# solenoidcontroller.net
KiCad netlist of a schematic drawn in EAGLE
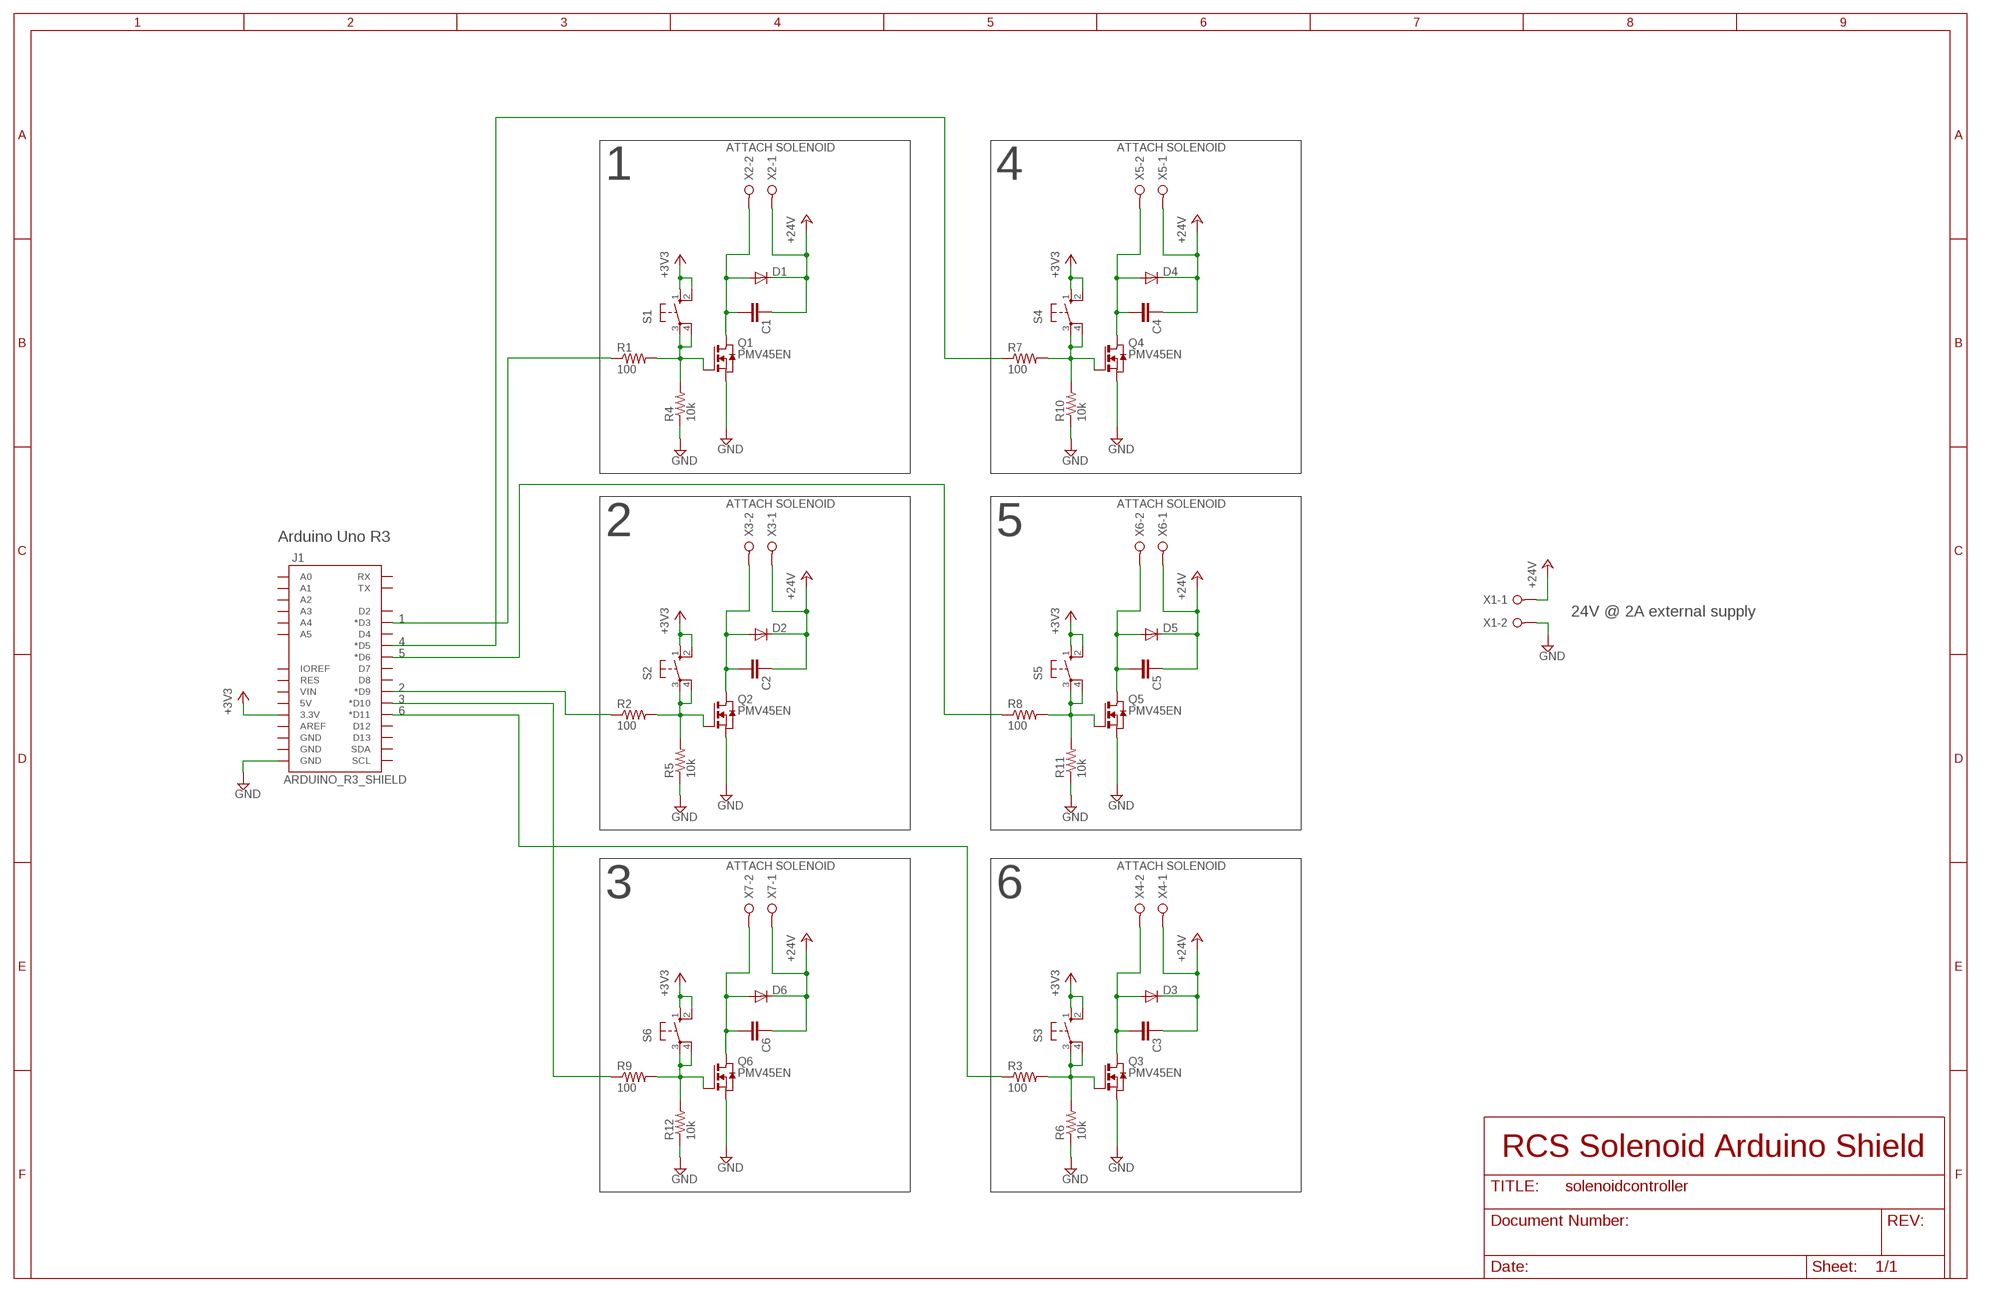
[diagram p0: schematic, sheet 1]

(export (version "E")
  (design (tool "Eeschema 10.0.6"))
  (components
    (comp (ref "C1")
      (value "C-EUC0603")
      (footprint "eagle-import:C0603")
      (libsource (lib "eagle-import") (part "C-EUC0603"))
    )
    (comp (ref "C2")
      (value "C-EUC0603")
      (footprint "eagle-import:C0603")
      (libsource (lib "eagle-import") (part "C-EUC0603"))
    )
    (comp (ref "C3")
      (value "C-EUC0603")
      (footprint "eagle-import:C0603")
      (libsource (lib "eagle-import") (part "C-EUC0603"))
    )
    (comp (ref "C4")
      (value "C-EUC0603")
      (footprint "eagle-import:C0603")
      (libsource (lib "eagle-import") (part "C-EUC0603"))
    )
    (comp (ref "C5")
      (value "C-EUC0603")
      (footprint "eagle-import:C0603")
      (libsource (lib "eagle-import") (part "C-EUC0603"))
    )
    (comp (ref "C6")
      (value "C-EUC0603")
      (footprint "eagle-import:C0603")
      (libsource (lib "eagle-import") (part "C-EUC0603"))
    )
    (comp (ref "D1")
      (value "DIODE-DO214BA")
      (footprint "eagle-import:DO214BA")
      (libsource (lib "eagle-import") (part "DIODE-DO214BA"))
    )
    (comp (ref "D2")
      (value "DIODE-DO214BA")
      (footprint "eagle-import:DO214BA")
      (libsource (lib "eagle-import") (part "DIODE-DO214BA"))
    )
    (comp (ref "D3")
      (value "DIODE-DO214BA")
      (footprint "eagle-import:DO214BA")
      (libsource (lib "eagle-import") (part "DIODE-DO214BA"))
    )
    (comp (ref "D4")
      (value "DIODE-DO214BA")
      (footprint "eagle-import:DO214BA")
      (libsource (lib "eagle-import") (part "DIODE-DO214BA"))
    )
    (comp (ref "D5")
      (value "DIODE-DO214BA")
      (footprint "eagle-import:DO214BA")
      (libsource (lib "eagle-import") (part "DIODE-DO214BA"))
    )
    (comp (ref "D6")
      (value "DIODE-DO214BA")
      (footprint "eagle-import:DO214BA")
      (libsource (lib "eagle-import") (part "DIODE-DO214BA"))
    )
    (comp (ref "J1")
      (value "ARDUINO_R3_SHIELD")
      (footprint "eagle-import:UNO_R3_SHIELD")
      (libsource (lib "eagle-import") (part "ARDUINO_R3_SHIELD"))
    )
    (comp (ref "Q1")
      (value "PMV45EN")
      (footprint "eagle-import:SOT23")
      (libsource (lib "eagle-import") (part "PMV45EN"))
    )
    (comp (ref "Q2")
      (value "PMV45EN")
      (footprint "eagle-import:SOT23")
      (libsource (lib "eagle-import") (part "PMV45EN"))
    )
    (comp (ref "Q3")
      (value "PMV45EN")
      (footprint "eagle-import:SOT23")
      (libsource (lib "eagle-import") (part "PMV45EN"))
    )
    (comp (ref "Q4")
      (value "PMV45EN")
      (footprint "eagle-import:SOT23")
      (libsource (lib "eagle-import") (part "PMV45EN"))
    )
    (comp (ref "Q5")
      (value "PMV45EN")
      (footprint "eagle-import:SOT23")
      (libsource (lib "eagle-import") (part "PMV45EN"))
    )
    (comp (ref "Q6")
      (value "PMV45EN")
      (footprint "eagle-import:SOT23")
      (libsource (lib "eagle-import") (part "PMV45EN"))
    )
    (comp (ref "R1")
      (value "100")
      (footprint "eagle-import:R0603")
      (libsource (lib "eagle-import") (part "R-US_R0603"))
    )
    (comp (ref "R2")
      (value "100")
      (footprint "eagle-import:R0603")
      (libsource (lib "eagle-import") (part "R-US_R0603"))
    )
    (comp (ref "R3")
      (value "100")
      (footprint "eagle-import:R0603")
      (libsource (lib "eagle-import") (part "R-US_R0603"))
    )
    (comp (ref "R4")
      (value "10k")
      (footprint "eagle-import:R0603")
      (libsource (lib "eagle-import") (part "R-US_R0603"))
    )
    (comp (ref "R5")
      (value "10k")
      (footprint "eagle-import:R0603")
      (libsource (lib "eagle-import") (part "R-US_R0603"))
    )
    (comp (ref "R6")
      (value "10k")
      (footprint "eagle-import:R0603")
      (libsource (lib "eagle-import") (part "R-US_R0603"))
    )
    (comp (ref "R7")
      (value "100")
      (footprint "eagle-import:R0603")
      (libsource (lib "eagle-import") (part "R-US_R0603"))
    )
    (comp (ref "R8")
      (value "100")
      (footprint "eagle-import:R0603")
      (libsource (lib "eagle-import") (part "R-US_R0603"))
    )
    (comp (ref "R9")
      (value "100")
      (footprint "eagle-import:R0603")
      (libsource (lib "eagle-import") (part "R-US_R0603"))
    )
    (comp (ref "R10")
      (value "10k")
      (footprint "eagle-import:R0603")
      (libsource (lib "eagle-import") (part "R-US_R0603"))
    )
    (comp (ref "R11")
      (value "10k")
      (footprint "eagle-import:R0603")
      (libsource (lib "eagle-import") (part "R-US_R0603"))
    )
    (comp (ref "R12")
      (value "10k")
      (footprint "eagle-import:R0603")
      (libsource (lib "eagle-import") (part "R-US_R0603"))
    )
    (comp (ref "S1")
      (value "10-XX")
      (footprint "eagle-import:B3F-10XX")
      (fields (field (name "MPN") "B3F-1000"))
      (libsource (lib "eagle-import") (part "10-XX"))
    )
    (comp (ref "S2")
      (value "10-XX")
      (footprint "eagle-import:B3F-10XX")
      (fields (field (name "MPN") "B3F-1000"))
      (libsource (lib "eagle-import") (part "10-XX"))
    )
    (comp (ref "S3")
      (value "10-XX")
      (footprint "eagle-import:B3F-10XX")
      (fields (field (name "MPN") "B3F-1000"))
      (libsource (lib "eagle-import") (part "10-XX"))
    )
    (comp (ref "S4")
      (value "10-XX")
      (footprint "eagle-import:B3F-10XX")
      (fields (field (name "MPN") "B3F-1000"))
      (libsource (lib "eagle-import") (part "10-XX"))
    )
    (comp (ref "S5")
      (value "10-XX")
      (footprint "eagle-import:B3F-10XX")
      (fields (field (name "MPN") "B3F-1000"))
      (libsource (lib "eagle-import") (part "10-XX"))
    )
    (comp (ref "S6")
      (value "10-XX")
      (footprint "eagle-import:B3F-10XX")
      (fields (field (name "MPN") "B3F-1000"))
      (libsource (lib "eagle-import") (part "10-XX"))
    )
    (comp (ref "X1")
      (value "W237-02P")
      (footprint "eagle-import:W237-132")
      (libsource (lib "eagle-import") (part "W237-02P"))
    )
    (comp (ref "X2")
      (value "W237-02P")
      (footprint "eagle-import:W237-132")
      (libsource (lib "eagle-import") (part "W237-02P"))
    )
    (comp (ref "X3")
      (value "W237-02P")
      (footprint "eagle-import:W237-132")
      (libsource (lib "eagle-import") (part "W237-02P"))
    )
    (comp (ref "X4")
      (value "W237-02P")
      (footprint "eagle-import:W237-132")
      (libsource (lib "eagle-import") (part "W237-02P"))
    )
    (comp (ref "X5")
      (value "W237-02P")
      (footprint "eagle-import:W237-132")
      (libsource (lib "eagle-import") (part "W237-02P"))
    )
    (comp (ref "X6")
      (value "W237-02P")
      (footprint "eagle-import:W237-132")
      (libsource (lib "eagle-import") (part "W237-02P"))
    )
    (comp (ref "X7")
      (value "W237-02P")
      (footprint "eagle-import:W237-132")
      (libsource (lib "eagle-import") (part "W237-02P"))
    )
  )
  (nets
    (net (code "1") (name "+3V3") (class "Default")
      (node (ref "J1") (pin "3.3V") (pinfunction "3.3V_3.3V") (pintype "bidirectional"))
      (node (ref "S1") (pin "1") (pinfunction "S_1") (pintype "passive"))
      (node (ref "S1") (pin "2") (pinfunction "S1_2") (pintype "passive"))
      (node (ref "S2") (pin "1") (pinfunction "S_1") (pintype "passive"))
      (node (ref "S2") (pin "2") (pinfunction "S1_2") (pintype "passive"))
      (node (ref "S3") (pin "1") (pinfunction "S_1") (pintype "passive"))
      (node (ref "S3") (pin "2") (pinfunction "S1_2") (pintype "passive"))
      (node (ref "S4") (pin "1") (pinfunction "S_1") (pintype "passive"))
      (node (ref "S4") (pin "2") (pinfunction "S1_2") (pintype "passive"))
      (node (ref "S5") (pin "1") (pinfunction "S_1") (pintype "passive"))
      (node (ref "S5") (pin "2") (pinfunction "S1_2") (pintype "passive"))
      (node (ref "S6") (pin "1") (pinfunction "S_1") (pintype "passive"))
      (node (ref "S6") (pin "2") (pinfunction "S1_2") (pintype "passive"))
    )
    (net (code "2") (name "+24V") (class "Default")
      (node (ref "C1") (pin "1") (pinfunction "1_1") (pintype "passive"))
      (node (ref "C2") (pin "1") (pinfunction "1_1") (pintype "passive"))
      (node (ref "C3") (pin "1") (pinfunction "1_1") (pintype "passive"))
      (node (ref "C4") (pin "1") (pinfunction "1_1") (pintype "passive"))
      (node (ref "C5") (pin "1") (pinfunction "1_1") (pintype "passive"))
      (node (ref "C6") (pin "1") (pinfunction "1_1") (pintype "passive"))
      (node (ref "D1") (pin "C") (pinfunction "C_C") (pintype "passive"))
      (node (ref "D2") (pin "C") (pinfunction "C_C") (pintype "passive"))
      (node (ref "D3") (pin "C") (pinfunction "C_C") (pintype "passive"))
      (node (ref "D4") (pin "C") (pinfunction "C_C") (pintype "passive"))
      (node (ref "D5") (pin "C") (pinfunction "C_C") (pintype "passive"))
      (node (ref "D6") (pin "C") (pinfunction "C_C") (pintype "passive"))
      (node (ref "X1") (pin "1") (pinfunction "KL_1") (pintype "passive"))
      (node (ref "X2") (pin "1") (pinfunction "KL_1") (pintype "passive"))
      (node (ref "X3") (pin "1") (pinfunction "KL_1") (pintype "passive"))
      (node (ref "X4") (pin "1") (pinfunction "KL_1") (pintype "passive"))
      (node (ref "X5") (pin "1") (pinfunction "KL_1") (pintype "passive"))
      (node (ref "X6") (pin "1") (pinfunction "KL_1") (pintype "passive"))
      (node (ref "X7") (pin "1") (pinfunction "KL_1") (pintype "passive"))
    )
    (net (code "3") (name "/1") (class "Default")
      (node (ref "J1") (pin "D3") (pinfunction "*D3_D3") (pintype "bidirectional"))
      (node (ref "R1") (pin "1") (pinfunction "1_1") (pintype "passive"))
    )
    (net (code "4") (name "/2") (class "Default")
      (node (ref "J1") (pin "D9") (pinfunction "*D9_D9") (pintype "bidirectional"))
      (node (ref "R2") (pin "1") (pinfunction "1_1") (pintype "passive"))
    )
    (net (code "5") (name "/3") (class "Default")
      (node (ref "J1") (pin "D10") (pinfunction "*D10_D10") (pintype "bidirectional"))
      (node (ref "R9") (pin "1") (pinfunction "1_1") (pintype "passive"))
    )
    (net (code "6") (name "/4") (class "Default")
      (node (ref "J1") (pin "D5") (pinfunction "*D5_D5") (pintype "bidirectional"))
      (node (ref "R7") (pin "1") (pinfunction "1_1") (pintype "passive"))
    )
    (net (code "7") (name "/5") (class "Default")
      (node (ref "J1") (pin "D6") (pinfunction "*D6_D6") (pintype "bidirectional"))
      (node (ref "R8") (pin "1") (pinfunction "1_1") (pintype "passive"))
    )
    (net (code "8") (name "/6") (class "Default")
      (node (ref "J1") (pin "D11") (pinfunction "*D11_D11") (pintype "bidirectional"))
      (node (ref "R3") (pin "1") (pinfunction "1_1") (pintype "passive"))
    )
    (net (code "9") (name "GND") (class "Default")
      (node (ref "J1") (pin "GND@0") (pinfunction "GND_GND@0") (pintype "bidirectional"))
      (node (ref "Q1") (pin "2") (pinfunction "S_2") (pintype "passive"))
      (node (ref "Q2") (pin "2") (pinfunction "S_2") (pintype "passive"))
      (node (ref "Q3") (pin "2") (pinfunction "S_2") (pintype "passive"))
      (node (ref "Q4") (pin "2") (pinfunction "S_2") (pintype "passive"))
      (node (ref "Q5") (pin "2") (pinfunction "S_2") (pintype "passive"))
      (node (ref "Q6") (pin "2") (pinfunction "S_2") (pintype "passive"))
      (node (ref "R10") (pin "1") (pinfunction "1_1") (pintype "passive"))
      (node (ref "R11") (pin "1") (pinfunction "1_1") (pintype "passive"))
      (node (ref "R12") (pin "1") (pinfunction "1_1") (pintype "passive"))
      (node (ref "R4") (pin "1") (pinfunction "1_1") (pintype "passive"))
      (node (ref "R5") (pin "1") (pinfunction "1_1") (pintype "passive"))
      (node (ref "R6") (pin "1") (pinfunction "1_1") (pintype "passive"))
      (node (ref "X1") (pin "2") (pinfunction "KL_2") (pintype "passive"))
    )
    (net (code "10") (name "Net-(Q1-D)") (class "Default")
      (node (ref "C1") (pin "2") (pinfunction "2_2") (pintype "passive"))
      (node (ref "D1") (pin "A") (pinfunction "A_A") (pintype "passive"))
      (node (ref "Q1") (pin "3") (pinfunction "D_3") (pintype "passive"))
      (node (ref "X2") (pin "2") (pinfunction "KL_2") (pintype "passive"))
    )
    (net (code "11") (name "Net-(Q1-G)") (class "Default")
      (node (ref "Q1") (pin "1") (pinfunction "G_1") (pintype "passive"))
      (node (ref "R1") (pin "2") (pinfunction "2_2") (pintype "passive"))
      (node (ref "R4") (pin "2") (pinfunction "2_2") (pintype "passive"))
      (node (ref "S1") (pin "3") (pinfunction "P_3") (pintype "passive"))
      (node (ref "S1") (pin "4") (pinfunction "P1_4") (pintype "passive"))
    )
    (net (code "12") (name "Net-(Q2-D)") (class "Default")
      (node (ref "C2") (pin "2") (pinfunction "2_2") (pintype "passive"))
      (node (ref "D2") (pin "A") (pinfunction "A_A") (pintype "passive"))
      (node (ref "Q2") (pin "3") (pinfunction "D_3") (pintype "passive"))
      (node (ref "X3") (pin "2") (pinfunction "KL_2") (pintype "passive"))
    )
    (net (code "13") (name "Net-(Q2-G)") (class "Default")
      (node (ref "Q2") (pin "1") (pinfunction "G_1") (pintype "passive"))
      (node (ref "R2") (pin "2") (pinfunction "2_2") (pintype "passive"))
      (node (ref "R5") (pin "2") (pinfunction "2_2") (pintype "passive"))
      (node (ref "S2") (pin "3") (pinfunction "P_3") (pintype "passive"))
      (node (ref "S2") (pin "4") (pinfunction "P1_4") (pintype "passive"))
    )
    (net (code "14") (name "Net-(Q3-D)") (class "Default")
      (node (ref "C3") (pin "2") (pinfunction "2_2") (pintype "passive"))
      (node (ref "D3") (pin "A") (pinfunction "A_A") (pintype "passive"))
      (node (ref "Q3") (pin "3") (pinfunction "D_3") (pintype "passive"))
      (node (ref "X4") (pin "2") (pinfunction "KL_2") (pintype "passive"))
    )
    (net (code "15") (name "Net-(Q3-G)") (class "Default")
      (node (ref "Q3") (pin "1") (pinfunction "G_1") (pintype "passive"))
      (node (ref "R3") (pin "2") (pinfunction "2_2") (pintype "passive"))
      (node (ref "R6") (pin "2") (pinfunction "2_2") (pintype "passive"))
      (node (ref "S3") (pin "3") (pinfunction "P_3") (pintype "passive"))
      (node (ref "S3") (pin "4") (pinfunction "P1_4") (pintype "passive"))
    )
    (net (code "16") (name "Net-(Q4-D)") (class "Default")
      (node (ref "C4") (pin "2") (pinfunction "2_2") (pintype "passive"))
      (node (ref "D4") (pin "A") (pinfunction "A_A") (pintype "passive"))
      (node (ref "Q4") (pin "3") (pinfunction "D_3") (pintype "passive"))
      (node (ref "X5") (pin "2") (pinfunction "KL_2") (pintype "passive"))
    )
    (net (code "17") (name "Net-(Q4-G)") (class "Default")
      (node (ref "Q4") (pin "1") (pinfunction "G_1") (pintype "passive"))
      (node (ref "R10") (pin "2") (pinfunction "2_2") (pintype "passive"))
      (node (ref "R7") (pin "2") (pinfunction "2_2") (pintype "passive"))
      (node (ref "S4") (pin "3") (pinfunction "P_3") (pintype "passive"))
      (node (ref "S4") (pin "4") (pinfunction "P1_4") (pintype "passive"))
    )
    (net (code "18") (name "Net-(Q5-D)") (class "Default")
      (node (ref "C5") (pin "2") (pinfunction "2_2") (pintype "passive"))
      (node (ref "D5") (pin "A") (pinfunction "A_A") (pintype "passive"))
      (node (ref "Q5") (pin "3") (pinfunction "D_3") (pintype "passive"))
      (node (ref "X6") (pin "2") (pinfunction "KL_2") (pintype "passive"))
    )
    (net (code "19") (name "Net-(Q5-G)") (class "Default")
      (node (ref "Q5") (pin "1") (pinfunction "G_1") (pintype "passive"))
      (node (ref "R11") (pin "2") (pinfunction "2_2") (pintype "passive"))
      (node (ref "R8") (pin "2") (pinfunction "2_2") (pintype "passive"))
      (node (ref "S5") (pin "3") (pinfunction "P_3") (pintype "passive"))
      (node (ref "S5") (pin "4") (pinfunction "P1_4") (pintype "passive"))
    )
    (net (code "20") (name "Net-(Q6-D)") (class "Default")
      (node (ref "C6") (pin "2") (pinfunction "2_2") (pintype "passive"))
      (node (ref "D6") (pin "A") (pinfunction "A_A") (pintype "passive"))
      (node (ref "Q6") (pin "3") (pinfunction "D_3") (pintype "passive"))
      (node (ref "X7") (pin "2") (pinfunction "KL_2") (pintype "passive"))
    )
    (net (code "21") (name "Net-(Q6-G)") (class "Default")
      (node (ref "Q6") (pin "1") (pinfunction "G_1") (pintype "passive"))
      (node (ref "R12") (pin "2") (pinfunction "2_2") (pintype "passive"))
      (node (ref "R9") (pin "2") (pinfunction "2_2") (pintype "passive"))
      (node (ref "S6") (pin "3") (pinfunction "P_3") (pintype "passive"))
      (node (ref "S6") (pin "4") (pinfunction "P1_4") (pintype "passive"))
    )
    (net (code "22") (name "unconnected-(J1-GND-PadGND@1)") (class "Default")
      (node (ref "J1") (pin "GND@1") (pinfunction "GND_GND@1") (pintype "bidirectional"))
    )
    (net (code "23") (name "unconnected-(J1-GND-PadGND@2)") (class "Default")
      (node (ref "J1") (pin "GND@2") (pinfunction "GND_GND@2") (pintype "bidirectional"))
    )
    (net (code "24") (name "unconnected-(J1-Pad5V)") (class "Default")
      (node (ref "J1") (pin "5V") (pinfunction "5V_5V") (pintype "bidirectional"))
    )
    (net (code "25") (name "unconnected-(J1-PadA0)") (class "Default")
      (node (ref "J1") (pin "A0") (pinfunction "A0_A0") (pintype "bidirectional"))
    )
    (net (code "26") (name "unconnected-(J1-PadA1)") (class "Default")
      (node (ref "J1") (pin "A1") (pinfunction "A1_A1") (pintype "bidirectional"))
    )
    (net (code "27") (name "unconnected-(J1-PadA2)") (class "Default")
      (node (ref "J1") (pin "A2") (pinfunction "A2_A2") (pintype "bidirectional"))
    )
    (net (code "28") (name "unconnected-(J1-PadA3)") (class "Default")
      (node (ref "J1") (pin "A3") (pinfunction "A3_A3") (pintype "bidirectional"))
    )
    (net (code "29") (name "unconnected-(J1-PadA4)") (class "Default")
      (node (ref "J1") (pin "A4") (pinfunction "A4_A4") (pintype "bidirectional"))
    )
    (net (code "30") (name "unconnected-(J1-PadA5)") (class "Default")
      (node (ref "J1") (pin "A5") (pinfunction "A5_A5") (pintype "bidirectional"))
    )
    (net (code "31") (name "unconnected-(J1-PadAREF)") (class "Default")
      (node (ref "J1") (pin "AREF") (pinfunction "AREF_AREF") (pintype "bidirectional"))
    )
    (net (code "32") (name "unconnected-(J1-PadD2)") (class "Default")
      (node (ref "J1") (pin "D2") (pinfunction "D2_D2") (pintype "bidirectional"))
    )
    (net (code "33") (name "unconnected-(J1-PadD4)") (class "Default")
      (node (ref "J1") (pin "D4") (pinfunction "D4_D4") (pintype "bidirectional"))
    )
    (net (code "34") (name "unconnected-(J1-PadD7)") (class "Default")
      (node (ref "J1") (pin "D7") (pinfunction "D7_D7") (pintype "bidirectional"))
    )
    (net (code "35") (name "unconnected-(J1-PadD8)") (class "Default")
      (node (ref "J1") (pin "D8") (pinfunction "D8_D8") (pintype "bidirectional"))
    )
    (net (code "36") (name "unconnected-(J1-PadD12)") (class "Default")
      (node (ref "J1") (pin "D12") (pinfunction "D12_D12") (pintype "bidirectional"))
    )
    (net (code "37") (name "unconnected-(J1-PadD13)") (class "Default")
      (node (ref "J1") (pin "D13") (pinfunction "D13_D13") (pintype "bidirectional"))
    )
    (net (code "38") (name "unconnected-(J1-PadIOREF)") (class "Default")
      (node (ref "J1") (pin "IOREF") (pinfunction "IOREF_IOREF") (pintype "bidirectional"))
    )
    (net (code "39") (name "unconnected-(J1-PadRES)") (class "Default")
      (node (ref "J1") (pin "RES") (pinfunction "RES_RES") (pintype "bidirectional"))
    )
    (net (code "40") (name "unconnected-(J1-PadRX)") (class "Default")
      (node (ref "J1") (pin "RX") (pinfunction "RX_RX") (pintype "bidirectional"))
    )
    (net (code "41") (name "unconnected-(J1-PadSCL)") (class "Default")
      (node (ref "J1") (pin "SCL") (pinfunction "SCL_SCL") (pintype "bidirectional"))
    )
    (net (code "42") (name "unconnected-(J1-PadSDA)") (class "Default")
      (node (ref "J1") (pin "SDA") (pinfunction "SDA_SDA") (pintype "bidirectional"))
    )
    (net (code "43") (name "unconnected-(J1-PadTX)") (class "Default")
      (node (ref "J1") (pin "TX") (pinfunction "TX_TX") (pintype "bidirectional"))
    )
    (net (code "44") (name "unconnected-(J1-PadVIN)") (class "Default")
      (node (ref "J1") (pin "VIN") (pinfunction "VIN_VIN") (pintype "bidirectional"))
    )
  )
)
